# 06_SAMA7G54-PMIC.net
KiCad netlist of a schematic drawn in Altium Designer
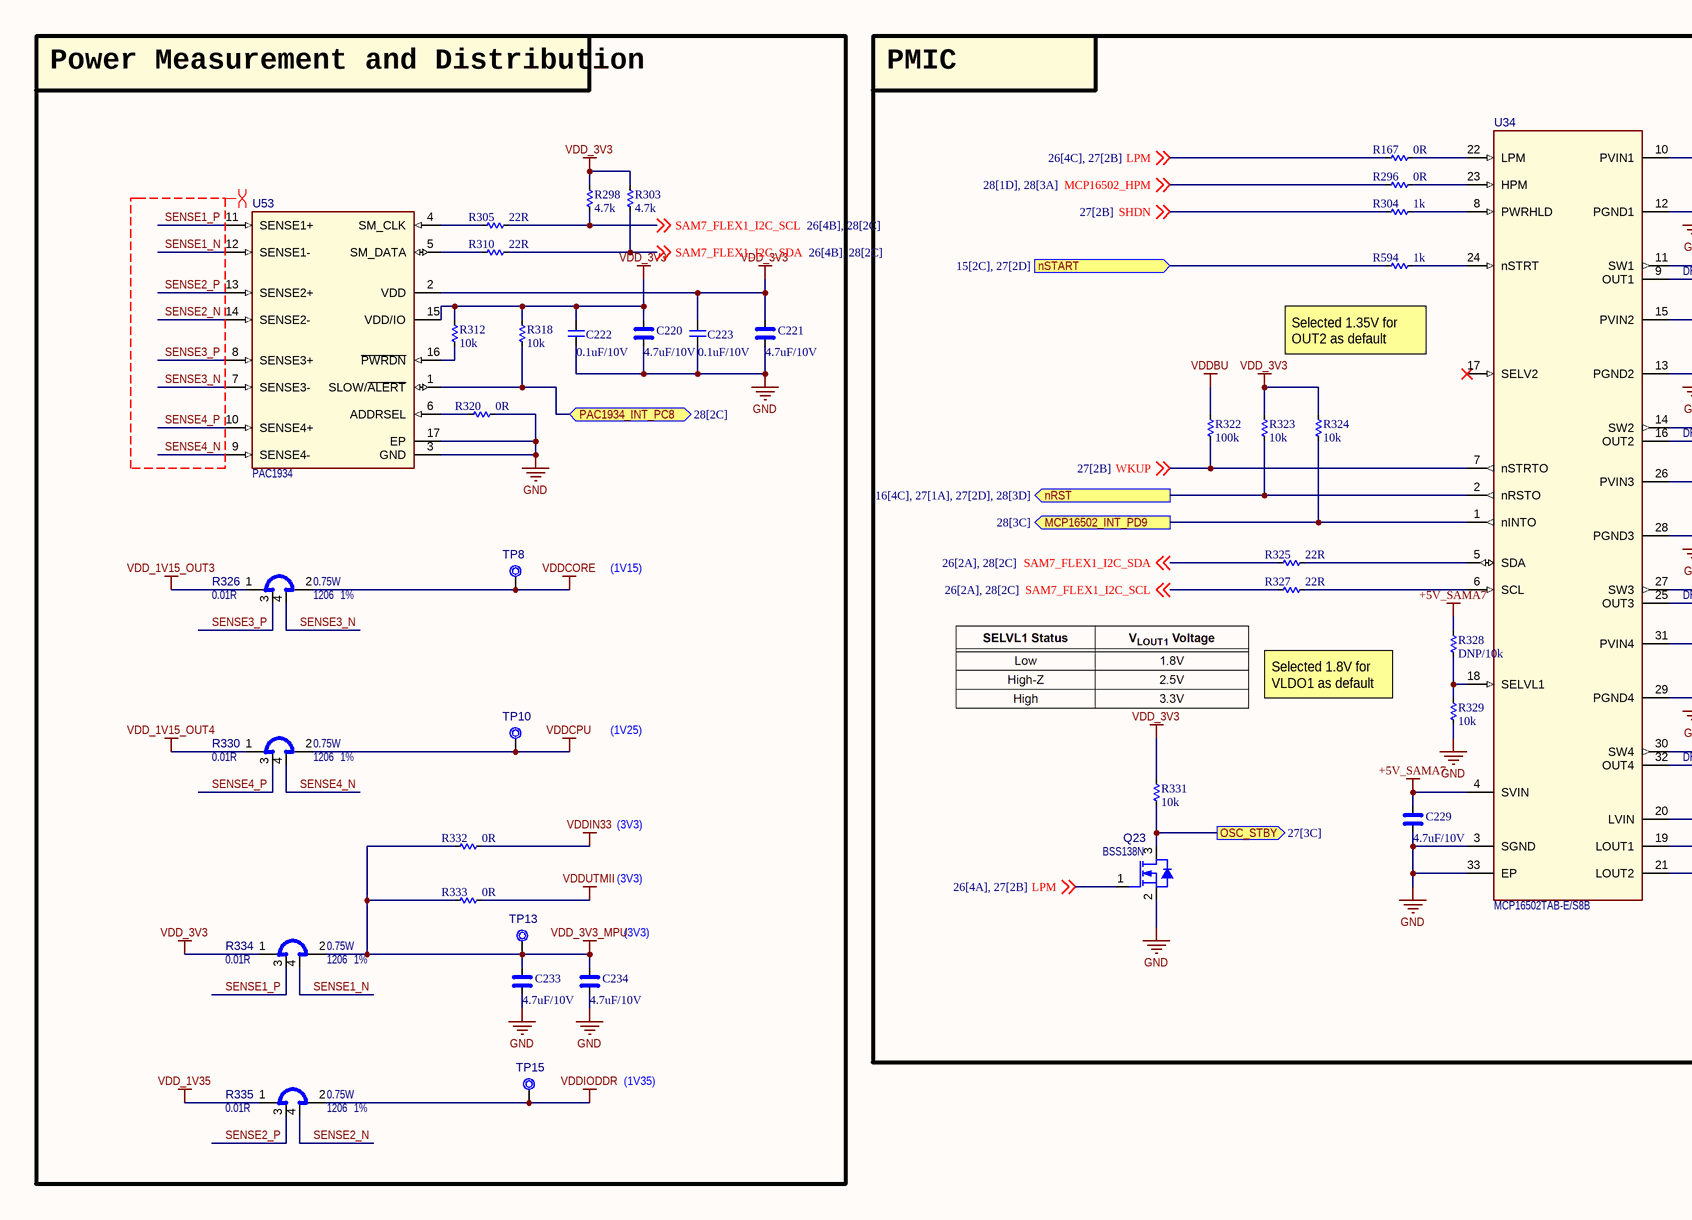
[diagram p0: 06_SAMA7G54-PMIC.SchDoc, left]
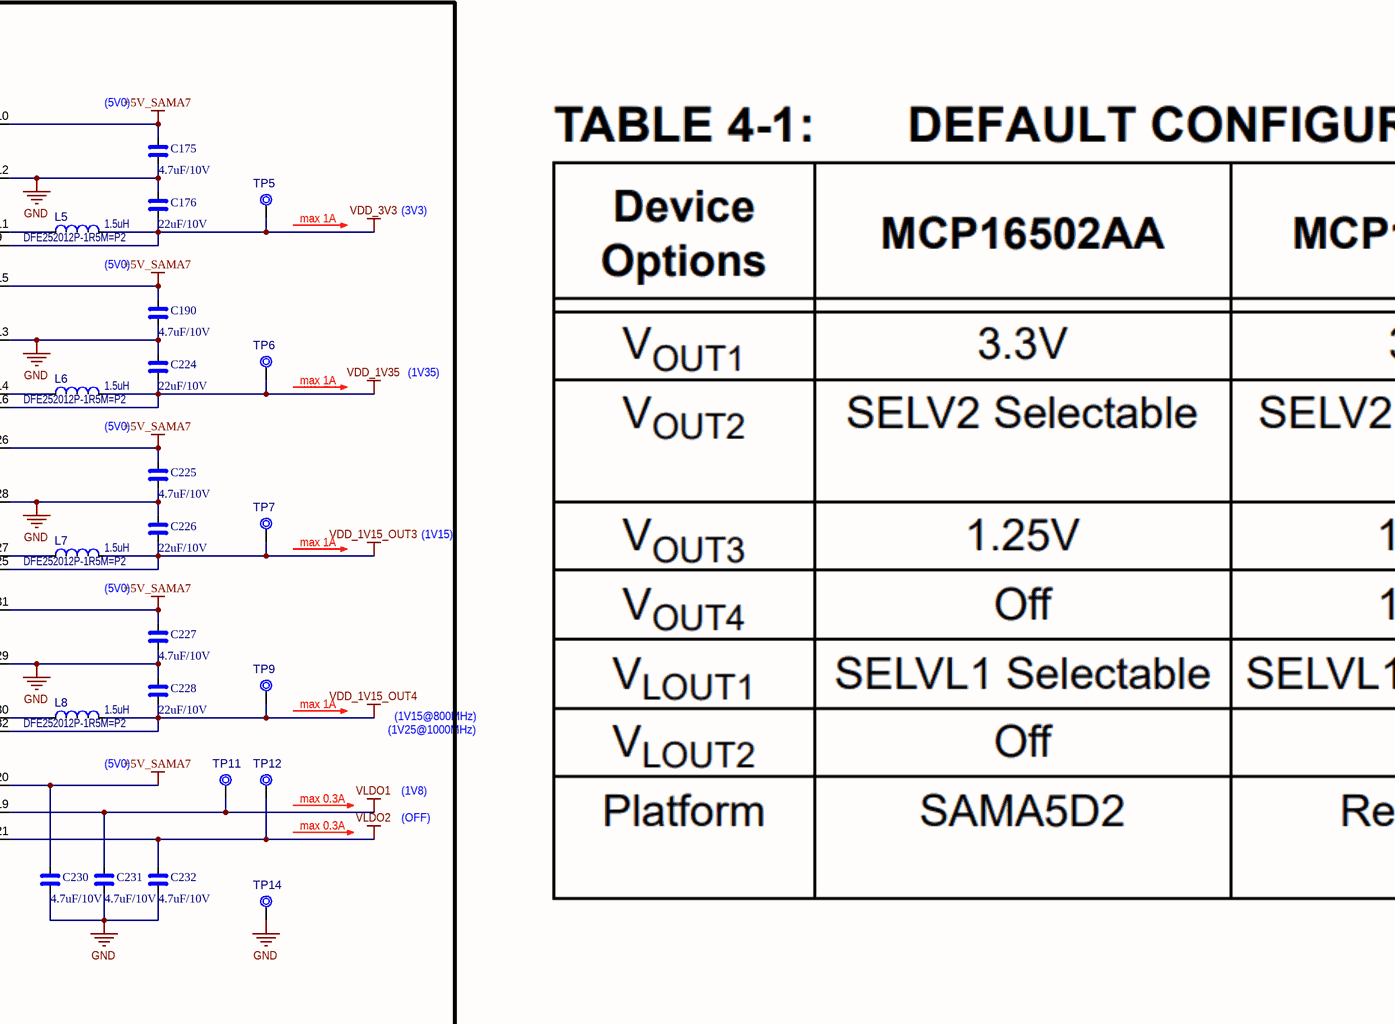
[diagram p1: 06_SAMA7G54-PMIC.SchDoc, middle]
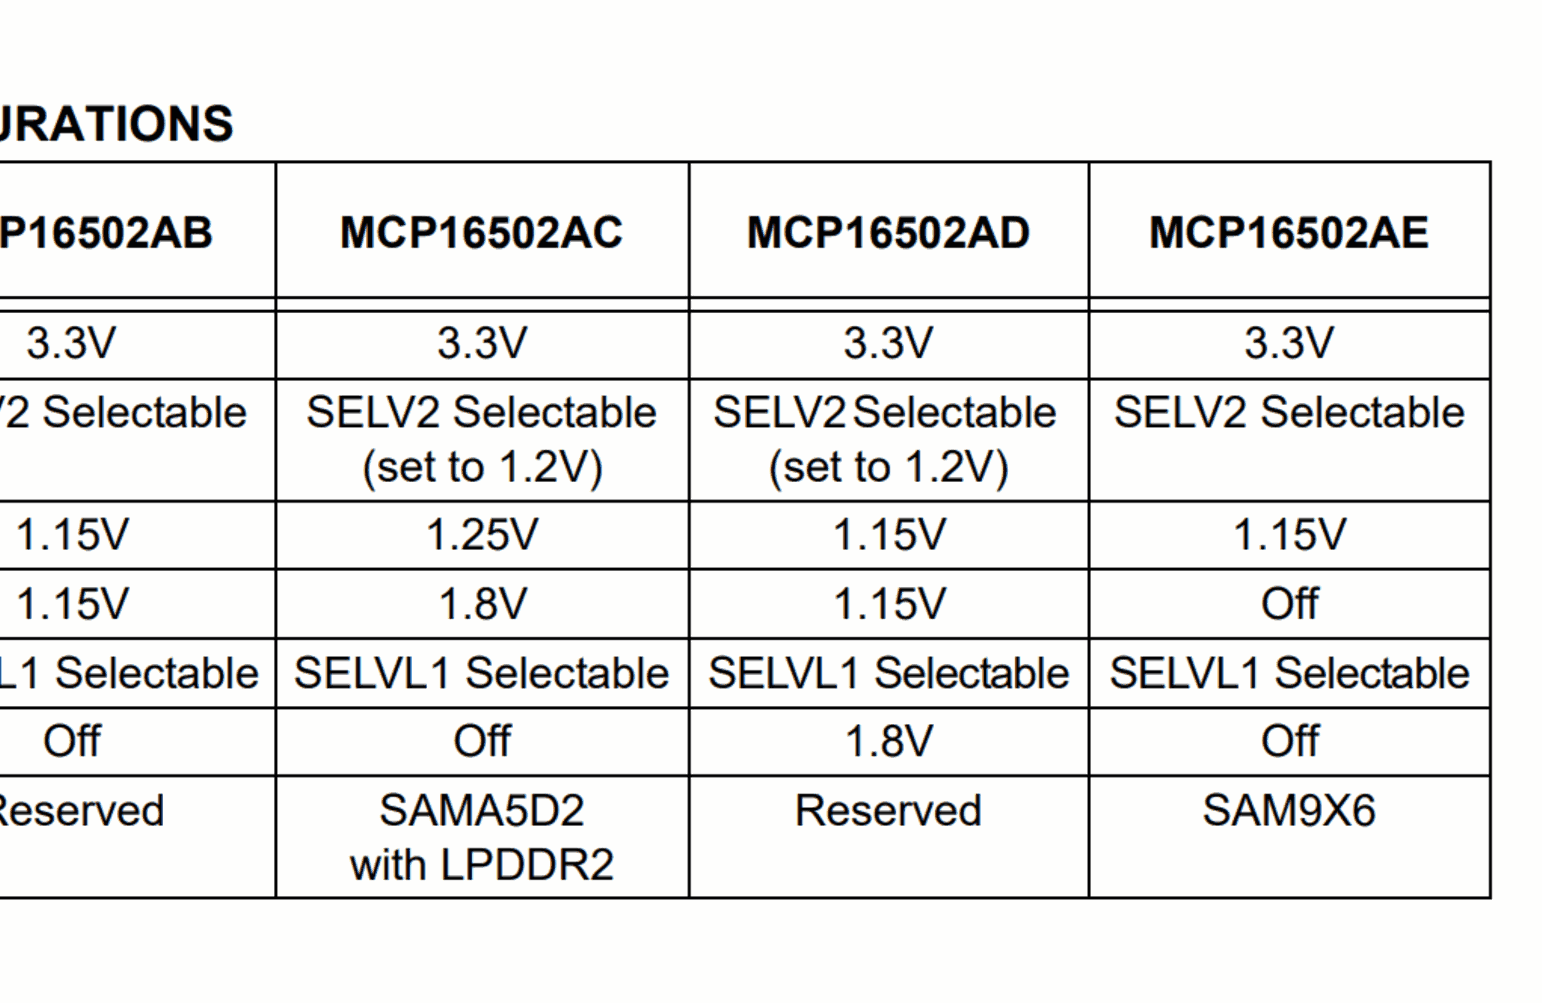
[diagram p2: 06_SAMA7G54-PMIC.SchDoc, right]

(export (version "E")
  (design (tool "Eeschema 10.0.6"))
  (components
    (comp (ref "C175")
      (value "4.7uF/10V")
      (footprint "CAP_C_1005X50_L")
      (description "CAP CHIP High Value")
      (libsource (lib "LABLIB") (part "_CAP_C_High_2"))
    )
    (comp (ref "C176")
      (value "22uF/10V")
      (footprint "CAP_C_1608X80")
      (description "CAP CHIP High Value")
      (libsource (lib "LABLIB") (part "_CAP_C_High_2"))
    )
    (comp (ref "C190")
      (value "4.7uF/10V")
      (footprint "CAP_C_1005X50_L")
      (description "CAP CHIP High Value")
      (libsource (lib "LABLIB") (part "_CAP_C_High_2"))
    )
    (comp (ref "C220")
      (value "4.7uF/10V")
      (footprint "CAP_C_1005X60")
      (description "CAP CHIP High Value")
      (libsource (lib "LABLIB") (part "_CAP_C_High_2"))
    )
    (comp (ref "C221")
      (value "4.7uF/10V")
      (footprint "CAP_C_1005X60")
      (description "CAP CHIP High Value")
      (libsource (lib "LABLIB") (part "_CAP_C_High_2"))
    )
    (comp (ref "C222")
      (value "0.1uF/10V")
      (footprint "CAP_C_1005X60")
      (description "CAP CHIP")
      (libsource (lib "LABLIB") (part "_CAP_C_2"))
    )
    (comp (ref "C223")
      (value "0.1uF/10V")
      (footprint "CAP_C_1005X60")
      (description "CAP CHIP")
      (libsource (lib "LABLIB") (part "_CAP_C_2"))
    )
    (comp (ref "C224")
      (value "22uF/10V")
      (footprint "CAP_C_1608X80")
      (description "CAP CHIP High Value")
      (libsource (lib "LABLIB") (part "_CAP_C_High_2"))
    )
    (comp (ref "C225")
      (value "4.7uF/10V")
      (footprint "CAP_C_1005X50_L")
      (description "CAP CHIP High Value")
      (libsource (lib "LABLIB") (part "_CAP_C_High_2"))
    )
    (comp (ref "C226")
      (value "22uF/10V")
      (footprint "CAP_C_1608X80")
      (description "CAP CHIP High Value")
      (libsource (lib "LABLIB") (part "_CAP_C_High_2"))
    )
    (comp (ref "C227")
      (value "4.7uF/10V")
      (footprint "CAP_C_1005X50_L")
      (description "CAP CHIP High Value")
      (libsource (lib "LABLIB") (part "_CAP_C_High_2"))
    )
    (comp (ref "C228")
      (value "22uF/10V")
      (footprint "CAP_C_1608X80")
      (description "CAP CHIP High Value")
      (libsource (lib "LABLIB") (part "_CAP_C_High_2"))
    )
    (comp (ref "C229")
      (value "4.7uF/10V")
      (footprint "CAP_C_1005X50_L")
      (description "CAP CHIP High Value")
      (libsource (lib "LABLIB") (part "_CAP_C_High_2"))
    )
    (comp (ref "C230")
      (value "4.7uF/10V")
      (footprint "CAP_C_1005X50_L")
      (description "CAP CHIP High Value")
      (libsource (lib "LABLIB") (part "_CAP_C_High_2"))
    )
    (comp (ref "C231")
      (value "4.7uF/10V")
      (footprint "CAP_C_1005X50_L")
      (description "CAP CHIP High Value")
      (libsource (lib "LABLIB") (part "_CAP_C_High_2"))
    )
    (comp (ref "C232")
      (value "4.7uF/10V")
      (footprint "CAP_C_1005X50_L")
      (description "CAP CHIP High Value")
      (libsource (lib "LABLIB") (part "_CAP_C_High_2"))
    )
    (comp (ref "C233")
      (value "4.7uF/10V")
      (footprint "CAP_C_1005X60")
      (description "CAP CHIP High Value")
      (libsource (lib "LABLIB") (part "_CAP_C_High_2"))
    )
    (comp (ref "C234")
      (value "4.7uF/10V")
      (footprint "CAP_C_1005X60")
      (description "CAP CHIP High Value")
      (libsource (lib "LABLIB") (part "_CAP_C_High_2"))
    )
    (comp (ref "L5")
      (value "1.5uH")
      (footprint "IND_C_1008")
      (description "Inductor")
      (fields
        (field (name "MANUFACTURER PART NUMBER 1") "DFE252012P-1R5M=P2")
        (field (name "OWNER") "Razvan Cristescu")
      )
      (libsource (lib "MCHP-CDB") (part "Inductor"))
    )
    (comp (ref "L6")
      (value "1.5uH")
      (footprint "IND_C_1008")
      (description "Inductor")
      (fields
        (field (name "MANUFACTURER PART NUMBER 1") "DFE252012P-1R5M=P2")
        (field (name "OWNER") "Razvan Cristescu")
      )
      (libsource (lib "MCHP-CDB") (part "Inductor"))
    )
    (comp (ref "L7")
      (value "1.5uH")
      (footprint "IND_C_1008")
      (description "Inductor")
      (fields
        (field (name "MANUFACTURER PART NUMBER 1") "DFE252012P-1R5M=P2")
        (field (name "OWNER") "Razvan Cristescu")
      )
      (libsource (lib "MCHP-CDB") (part "Inductor"))
    )
    (comp (ref "L8")
      (value "1.5uH")
      (footprint "IND_C_1008")
      (description "Inductor")
      (fields
        (field (name "MANUFACTURER PART NUMBER 1") "DFE252012P-1R5M=P2")
        (field (name "OWNER") "Razvan Cristescu")
      )
      (libsource (lib "MCHP-CDB") (part "Inductor"))
    )
    (comp (ref "Q23")
      (value "BSS138N")
      (footprint "SOT-23-3")
      (description "Transistor MOS")
      (fields
        (field (name "POWER") "0.36W")
        (field (name "VOLTAGE") "60V")
        (field (name "OWNER") "Dragos Danaila")
      )
      (libsource (lib "MCHP-CDB") (part "Transistor MOS-N GSD"))
    )
    (comp (ref "R167")
      (value "0R")
      (footprint "RES_C_1608X60")
      (description "RES")
      (libsource (lib "LABLIB") (part "_RES_B_2"))
    )
    (comp (ref "R296")
      (value "0R")
      (footprint "RES_C_1608X60")
      (description "RES")
      (libsource (lib "LABLIB") (part "_RES_B_2"))
    )
    (comp (ref "R298")
      (value "4.7k")
      (footprint "RES_C_1005X40")
      (description "RES")
      (libsource (lib "LABLIB") (part "_RES_B_2"))
    )
    (comp (ref "R303")
      (value "4.7k")
      (footprint "RES_C_1005X40")
      (description "RES")
      (libsource (lib "LABLIB") (part "_RES_B_2"))
    )
    (comp (ref "R304")
      (value "1k")
      (footprint "RES_C_1005X40")
      (description "RES")
      (libsource (lib "LABLIB") (part "_RES_B_2"))
    )
    (comp (ref "R305")
      (value "22R")
      (footprint "RES_C_1005X40")
      (description "RES")
      (libsource (lib "LABLIB") (part "_RES_B_2"))
    )
    (comp (ref "R310")
      (value "22R")
      (footprint "RES_C_1005X40")
      (description "RES")
      (libsource (lib "LABLIB") (part "_RES_B_2"))
    )
    (comp (ref "R312")
      (value "10k")
      (footprint "RES_C_1005X40")
      (description "RES")
      (libsource (lib "LABLIB") (part "_RES_B_2"))
    )
    (comp (ref "R318")
      (value "10k")
      (footprint "RES_C_1005X40")
      (description "RES")
      (libsource (lib "LABLIB") (part "_RES_B_2"))
    )
    (comp (ref "R320")
      (value "0R")
      (footprint "RES_C_1005X40")
      (description "RES")
      (libsource (lib "LABLIB") (part "_RES_B_2"))
    )
    (comp (ref "R322")
      (value "100k")
      (footprint "RES_C_1005X40")
      (description "RES")
      (libsource (lib "LABLIB") (part "_RES_B_2"))
    )
    (comp (ref "R323")
      (value "10k")
      (footprint "RES_C_1005X40")
      (description "RES")
      (libsource (lib "LABLIB") (part "_RES_B_2"))
    )
    (comp (ref "R324")
      (value "10k")
      (footprint "RES_C_1005X40")
      (description "RES")
      (libsource (lib "LABLIB") (part "_RES_B_2"))
    )
    (comp (ref "R325")
      (value "22R")
      (footprint "RES_C_0603X30")
      (description "RES")
      (libsource (lib "LABLIB") (part "_RES_B_2"))
    )
    (comp (ref "R326")
      (value "0.01R")
      (footprint "RES_C_1206_SHUNT")
      (description "Shunt")
      (fields
        (field (name "PACKAGE") "1206")
        (field (name "TOLERANCE") "1%")
        (field (name "POWER") "0.75W")
        (field (name "Comment") "Shunt 4 Pin")
        (field (name "OWNER") "Ciprian Abramov")
      )
      (libsource (lib "MCHP-CDB") (part "Shunt 4 Pin"))
    )
    (comp (ref "R327")
      (value "22R")
      (footprint "RES_C_0603X30")
      (description "RES")
      (libsource (lib "LABLIB") (part "_RES_B_2"))
    )
    (comp (ref "R328")
      (value "DNP/10k")
      (footprint "RES_C_1005X40")
      (description "RES")
      (libsource (lib "LABLIB") (part "_RES_B_2"))
    )
    (comp (ref "R329")
      (value "10k")
      (footprint "RES_C_1005X40")
      (description "RES")
      (libsource (lib "LABLIB") (part "_RES_B_2"))
    )
    (comp (ref "R330")
      (value "0.01R")
      (footprint "RES_C_1206_SHUNT")
      (description "Shunt")
      (fields
        (field (name "PACKAGE") "1206")
        (field (name "TOLERANCE") "1%")
        (field (name "POWER") "0.75W")
        (field (name "Comment") "Shunt 4 Pin")
        (field (name "OWNER") "Ciprian Abramov")
      )
      (libsource (lib "MCHP-CDB") (part "Shunt 4 Pin"))
    )
    (comp (ref "R331")
      (value "10k")
      (footprint "RES_C_1005X40")
      (description "RES")
      (libsource (lib "LABLIB") (part "_RES_B_2"))
    )
    (comp (ref "R332")
      (value "0R")
      (footprint "RES_C_1608X60")
      (description "RES")
      (libsource (lib "LABLIB") (part "_RES_B_2"))
    )
    (comp (ref "R333")
      (value "0R")
      (footprint "RES_C_1608X60")
      (description "RES")
      (libsource (lib "LABLIB") (part "_RES_B_2"))
    )
    (comp (ref "R334")
      (value "0.01R")
      (footprint "RES_C_1206_SHUNT")
      (description "Shunt")
      (fields
        (field (name "PACKAGE") "1206")
        (field (name "TOLERANCE") "1%")
        (field (name "POWER") "0.75W")
        (field (name "Comment") "Shunt 4 Pin")
        (field (name "OWNER") "Ciprian Abramov")
      )
      (libsource (lib "MCHP-CDB") (part "Shunt 4 Pin"))
    )
    (comp (ref "R335")
      (value "0.01R")
      (footprint "RES_C_1206_SHUNT")
      (description "Shunt")
      (fields
        (field (name "PACKAGE") "1206")
        (field (name "TOLERANCE") "1%")
        (field (name "POWER") "0.75W")
        (field (name "Comment") "Shunt 4 Pin")
        (field (name "OWNER") "Ciprian Abramov")
      )
      (libsource (lib "MCHP-CDB") (part "Shunt 4 Pin"))
    )
    (comp (ref "R594")
      (value "1k")
      (footprint "RES_C_1005X40")
      (description "RES")
      (libsource (lib "LABLIB") (part "_RES_B_2"))
    )
    (comp (ref "TP5")
      (value "Test Point No BOM")
      (footprint "Testpoint_80")
      (description "Test Point")
      (fields (field (name "OWNER") "Cristian Papuc"))
      (libsource (lib "MCHP-CDB") (part "Test Point No BOM"))
    )
    (comp (ref "TP6")
      (value "Test Point No BOM")
      (footprint "Testpoint_80")
      (description "Test Point")
      (fields (field (name "OWNER") "Cristian Papuc"))
      (libsource (lib "MCHP-CDB") (part "Test Point No BOM"))
    )
    (comp (ref "TP7")
      (value "Test Point No BOM")
      (footprint "Testpoint_80")
      (description "Test Point")
      (fields (field (name "OWNER") "Cristian Papuc"))
      (libsource (lib "MCHP-CDB") (part "Test Point No BOM"))
    )
    (comp (ref "TP8")
      (value "Test Point No BOM")
      (footprint "Testpoint_80")
      (description "Test Point")
      (fields (field (name "OWNER") "Cristian Papuc"))
      (libsource (lib "MCHP-CDB") (part "Test Point No BOM"))
    )
    (comp (ref "TP9")
      (value "Test Point No BOM")
      (footprint "Testpoint_80")
      (description "Test Point")
      (fields (field (name "OWNER") "Cristian Papuc"))
      (libsource (lib "MCHP-CDB") (part "Test Point No BOM"))
    )
    (comp (ref "TP10")
      (value "Test Point No BOM")
      (footprint "Testpoint_80")
      (description "Test Point")
      (fields (field (name "OWNER") "Cristian Papuc"))
      (libsource (lib "MCHP-CDB") (part "Test Point No BOM"))
    )
    (comp (ref "TP11")
      (value "Test Point No BOM")
      (footprint "Testpoint_80")
      (description "Test Point")
      (fields (field (name "OWNER") "Cristian Papuc"))
      (libsource (lib "MCHP-CDB") (part "Test Point No BOM"))
    )
    (comp (ref "TP12")
      (value "Test Point No BOM")
      (footprint "Testpoint_80")
      (description "Test Point")
      (fields (field (name "OWNER") "Cristian Papuc"))
      (libsource (lib "MCHP-CDB") (part "Test Point No BOM"))
    )
    (comp (ref "TP13")
      (value "Test Point No BOM")
      (footprint "Testpoint_80")
      (description "Test Point")
      (fields (field (name "OWNER") "Cristian Papuc"))
      (libsource (lib "MCHP-CDB") (part "Test Point No BOM"))
    )
    (comp (ref "TP14")
      (value "Test Point No BOM")
      (footprint "Testpoint_80")
      (description "Test Point")
      (fields (field (name "OWNER") "Cristian Papuc"))
      (libsource (lib "MCHP-CDB") (part "Test Point No BOM"))
    )
    (comp (ref "TP15")
      (value "Test Point No BOM")
      (footprint "Testpoint_80")
      (description "Test Point")
      (fields (field (name "OWNER") "Cristian Papuc"))
      (libsource (lib "MCHP-CDB") (part "Test Point No BOM"))
    )
    (comp (ref "U34")
      (value "MCP16502TAB-E/S8B")
      (footprint "QFN-32_5X5_EP3.7X3.7")
      (fields (field (name "OWNER") "Dragos Danaila"))
      (libsource (lib "MCHP-CDB") (part "MCP16502 QFN-32"))
    )
    (comp (ref "U53")
      (value "PAC1934")
      (footprint "UQFN-16_4X4_EP2.6X2.6")
      (fields (field (name "Comment") "PAC1934 UQFN-16") (field (name "OWNER") "Ciprian Abramov"))
      (libsource (lib "MCHP-CDB") (part "PAC1934 UQFN-16"))
    )
  )
  (nets
    (net (code "1") (name "+5V_SAMA7") (class "Default")
      (node (ref "C175") (pin "1") (pinfunction "1_1") (pintype "passive"))
      (node (ref "C190") (pin "1") (pinfunction "1_1") (pintype "passive"))
      (node (ref "C225") (pin "1") (pinfunction "1_1") (pintype "passive"))
      (node (ref "C227") (pin "1") (pinfunction "1_1") (pintype "passive"))
      (node (ref "C229") (pin "1") (pinfunction "1_1") (pintype "passive"))
      (node (ref "C230") (pin "1") (pinfunction "1_1") (pintype "passive"))
      (node (ref "R328") (pin "2") (pinfunction "2_2") (pintype "passive"))
      (node (ref "U34") (pin "10") (pinfunction "PVIN1_10") (pintype "power_in"))
      (node (ref "U34") (pin "15") (pinfunction "PVIN2_15") (pintype "power_in"))
      (node (ref "U34") (pin "20") (pinfunction "LVIN_20") (pintype "power_in"))
      (node (ref "U34") (pin "26") (pinfunction "PVIN3_26") (pintype "power_in"))
      (node (ref "U34") (pin "31") (pinfunction "PVIN4_31") (pintype "power_in"))
      (node (ref "U34") (pin "4") (pinfunction "SVIN_4") (pintype "power_in"))
    )
    (net (code "2") (name "/MCP16502_INT_PD9") (class "Default")
      (node (ref "R324") (pin "1") (pinfunction "1_1") (pintype "passive"))
      (node (ref "U34") (pin "1") (pinfunction "nINTO_1") (pintype "output"))
    )
    (net (code "3") (name "/OSC_STBY") (class "Default")
      (node (ref "Q23") (pin "3") (pinfunction "D_3") (pintype "passive"))
      (node (ref "R331") (pin "1") (pinfunction "1_1") (pintype "passive"))
    )
    (net (code "4") (name "/PAC1934_INT_PC8") (class "Default")
      (node (ref "R318") (pin "2") (pinfunction "2_2") (pintype "passive"))
      (node (ref "U53") (pin "1") (pinfunction "SLOW/~{ALERT}_1") (pintype "bidirectional"))
    )
    (net (code "5") (name "/SENSE1_N") (class "Default")
      (node (ref "R334") (pin "4") (pinfunction "4_4") (pintype "passive"))
      (node (ref "U53") (pin "12") (pinfunction "SENSE1-_12") (pintype "input"))
    )
    (net (code "6") (name "/SENSE1_P") (class "Default")
      (node (ref "R334") (pin "3") (pinfunction "3_3") (pintype "passive"))
      (node (ref "U53") (pin "11") (pinfunction "SENSE1+_11") (pintype "input"))
    )
    (net (code "7") (name "/SENSE2_N") (class "Default")
      (node (ref "R335") (pin "4") (pinfunction "4_4") (pintype "passive"))
      (node (ref "U53") (pin "14") (pinfunction "SENSE2-_14") (pintype "input"))
    )
    (net (code "8") (name "/SENSE2_P") (class "Default")
      (node (ref "R335") (pin "3") (pinfunction "3_3") (pintype "passive"))
      (node (ref "U53") (pin "13") (pinfunction "SENSE2+_13") (pintype "input"))
    )
    (net (code "9") (name "/SENSE3_N") (class "Default")
      (node (ref "R326") (pin "4") (pinfunction "4_4") (pintype "passive"))
      (node (ref "U53") (pin "7") (pinfunction "SENSE3-_7") (pintype "input"))
    )
    (net (code "10") (name "/SENSE3_P") (class "Default")
      (node (ref "R326") (pin "3") (pinfunction "3_3") (pintype "passive"))
      (node (ref "U53") (pin "8") (pinfunction "SENSE3+_8") (pintype "input"))
    )
    (net (code "11") (name "/SENSE4_N") (class "Default")
      (node (ref "R330") (pin "4") (pinfunction "4_4") (pintype "passive"))
      (node (ref "U53") (pin "9") (pinfunction "SENSE4-_9") (pintype "input"))
    )
    (net (code "12") (name "/SENSE4_P") (class "Default")
      (node (ref "R330") (pin "3") (pinfunction "3_3") (pintype "passive"))
      (node (ref "U53") (pin "10") (pinfunction "SENSE4+_10") (pintype "input"))
    )
    (net (code "13") (name "/nRST") (class "Default")
      (node (ref "R323") (pin "1") (pinfunction "1_1") (pintype "passive"))
      (node (ref "U34") (pin "2") (pinfunction "nRSTO_2") (pintype "output"))
    )
    (net (code "14") (name "/nSTART") (class "Default")
      (node (ref "R594") (pin "1") (pinfunction "1_1") (pintype "passive"))
    )
    (net (code "15") (name "GND") (class "Default")
      (node (ref "C175") (pin "2") (pinfunction "2_2") (pintype "passive"))
      (node (ref "C176") (pin "1") (pinfunction "1_1") (pintype "passive"))
      (node (ref "C190") (pin "2") (pinfunction "2_2") (pintype "passive"))
      (node (ref "C220") (pin "2") (pinfunction "2_2") (pintype "passive"))
      (node (ref "C221") (pin "2") (pinfunction "2_2") (pintype "passive"))
      (node (ref "C222") (pin "2") (pinfunction "2_2") (pintype "passive"))
      (node (ref "C223") (pin "2") (pinfunction "2_2") (pintype "passive"))
      (node (ref "C224") (pin "1") (pinfunction "1_1") (pintype "passive"))
      (node (ref "C225") (pin "2") (pinfunction "2_2") (pintype "passive"))
      (node (ref "C226") (pin "1") (pinfunction "1_1") (pintype "passive"))
      (node (ref "C227") (pin "2") (pinfunction "2_2") (pintype "passive"))
      (node (ref "C228") (pin "1") (pinfunction "1_1") (pintype "passive"))
      (node (ref "C229") (pin "2") (pinfunction "2_2") (pintype "passive"))
      (node (ref "C230") (pin "2") (pinfunction "2_2") (pintype "passive"))
      (node (ref "C231") (pin "2") (pinfunction "2_2") (pintype "passive"))
      (node (ref "C232") (pin "2") (pinfunction "2_2") (pintype "passive"))
      (node (ref "C233") (pin "2") (pinfunction "2_2") (pintype "passive"))
      (node (ref "C234") (pin "2") (pinfunction "2_2") (pintype "passive"))
      (node (ref "Q23") (pin "2") (pinfunction "S_2") (pintype "passive"))
      (node (ref "R320") (pin "2") (pinfunction "2_2") (pintype "passive"))
      (node (ref "R329") (pin "1") (pinfunction "1_1") (pintype "passive"))
      (node (ref "TP14") (pin "1") (pinfunction "1_1") (pintype "passive"))
      (node (ref "U34") (pin "12") (pinfunction "PGND1_12") (pintype "power_in"))
      (node (ref "U34") (pin "13") (pinfunction "PGND2_13") (pintype "power_in"))
      (node (ref "U34") (pin "28") (pinfunction "PGND3_28") (pintype "power_in"))
      (node (ref "U34") (pin "29") (pinfunction "PGND4_29") (pintype "power_in"))
      (node (ref "U34") (pin "3") (pinfunction "SGND_3") (pintype "power_in"))
      (node (ref "U34") (pin "33") (pinfunction "EP_33") (pintype "power_in"))
      (node (ref "U53") (pin "17") (pinfunction "EP_17") (pintype "passive"))
      (node (ref "U53") (pin "3") (pinfunction "GND_3") (pintype "power_in"))
    )
    (net (code "16") (name "LPM") (class "Default")
      (node (ref "Q23") (pin "1") (pinfunction "G_1") (pintype "passive"))
      (node (ref "R167") (pin "2") (pinfunction "2_2") (pintype "passive"))
    )
    (net (code "17") (name "MCP16502_HPM") (class "Default")
      (node (ref "R296") (pin "2") (pinfunction "2_2") (pintype "passive"))
    )
    (net (code "18") (name "Net-(L5-S)") (class "Default")
      (node (ref "L5") (pin "1") (pinfunction "S_1") (pintype "passive"))
      (node (ref "U34") (pin "11") (pinfunction "SW1_11") (pintype "output"))
    )
    (net (code "19") (name "Net-(L6-S)") (class "Default")
      (node (ref "L6") (pin "1") (pinfunction "S_1") (pintype "passive"))
      (node (ref "U34") (pin "14") (pinfunction "SW2_14") (pintype "output"))
    )
    (net (code "20") (name "Net-(L7-S)") (class "Default")
      (node (ref "L7") (pin "1") (pinfunction "S_1") (pintype "passive"))
      (node (ref "U34") (pin "27") (pinfunction "SW3_27") (pintype "output"))
    )
    (net (code "21") (name "Net-(L8-S)") (class "Default")
      (node (ref "L8") (pin "1") (pinfunction "S_1") (pintype "passive"))
      (node (ref "U34") (pin "30") (pinfunction "SW4_30") (pintype "output"))
    )
    (net (code "22") (name "Net-(U34-HPM)") (class "Default")
      (node (ref "R296") (pin "1") (pinfunction "1_1") (pintype "passive"))
      (node (ref "U34") (pin "23") (pinfunction "HPM_23") (pintype "input"))
    )
    (net (code "23") (name "Net-(U34-LPM)") (class "Default")
      (node (ref "R167") (pin "1") (pinfunction "1_1") (pintype "passive"))
      (node (ref "U34") (pin "22") (pinfunction "LPM_22") (pintype "input"))
    )
    (net (code "24") (name "Net-(U34-PWRHLD)") (class "Default")
      (node (ref "R304") (pin "2") (pinfunction "2_2") (pintype "passive"))
      (node (ref "U34") (pin "8") (pinfunction "PWRHLD_8") (pintype "input"))
    )
    (net (code "25") (name "Net-(U34-SCL)") (class "Default")
      (node (ref "R327") (pin "1") (pinfunction "1_1") (pintype "passive"))
      (node (ref "U34") (pin "6") (pinfunction "SCL_6") (pintype "input"))
    )
    (net (code "26") (name "Net-(U34-SDA)") (class "Default")
      (node (ref "R325") (pin "1") (pinfunction "1_1") (pintype "passive"))
      (node (ref "U34") (pin "5") (pinfunction "SDA_5") (pintype "bidirectional"))
    )
    (net (code "27") (name "Net-(U34-SELVL1)") (class "Default")
      (node (ref "R328") (pin "1") (pinfunction "1_1") (pintype "passive"))
      (node (ref "R329") (pin "2") (pinfunction "2_2") (pintype "passive"))
      (node (ref "U34") (pin "18") (pinfunction "SELVL1_18") (pintype "input"))
    )
    (net (code "28") (name "Net-(U34-nSTRT)") (class "Default")
      (node (ref "R594") (pin "2") (pinfunction "2_2") (pintype "passive"))
      (node (ref "U34") (pin "24") (pinfunction "nSTRT_24") (pintype "input"))
    )
    (net (code "29") (name "Net-(U53-ADDRSEL)") (class "Default")
      (node (ref "R320") (pin "1") (pinfunction "1_1") (pintype "passive"))
      (node (ref "U53") (pin "6") (pinfunction "ADDRSEL_6") (pintype "input"))
    )
    (net (code "30") (name "Net-(U53-SM_CLK)") (class "Default")
      (node (ref "R305") (pin "2") (pinfunction "2_2") (pintype "passive"))
      (node (ref "U53") (pin "4") (pinfunction "SM_CLK_4") (pintype "input"))
    )
    (net (code "31") (name "Net-(U53-SM_DATA)") (class "Default")
      (node (ref "R310") (pin "2") (pinfunction "2_2") (pintype "passive"))
      (node (ref "U53") (pin "5") (pinfunction "SM_DATA_5") (pintype "bidirectional"))
    )
    (net (code "32") (name "Net-(U53-~{PWRDN})") (class "Default")
      (node (ref "R312") (pin "2") (pinfunction "2_2") (pintype "passive"))
      (node (ref "U53") (pin "16") (pinfunction "~{PWRDN}_16") (pintype "input"))
    )
    (net (code "33") (name "SAM7_FLEX1_I2C_SCL") (class "Default")
      (node (ref "R298") (pin "2") (pinfunction "2_2") (pintype "passive"))
      (node (ref "R305") (pin "1") (pinfunction "1_1") (pintype "passive"))
      (node (ref "R327") (pin "2") (pinfunction "2_2") (pintype "passive"))
    )
    (net (code "34") (name "SAM7_FLEX1_I2C_SDA") (class "Default")
      (node (ref "R303") (pin "2") (pinfunction "2_2") (pintype "passive"))
      (node (ref "R310") (pin "1") (pinfunction "1_1") (pintype "passive"))
      (node (ref "R325") (pin "2") (pinfunction "2_2") (pintype "passive"))
    )
    (net (code "35") (name "SHDN") (class "Default")
      (node (ref "R304") (pin "1") (pinfunction "1_1") (pintype "passive"))
    )
    (net (code "36") (name "VDDBU") (class "Default")
      (node (ref "R322") (pin "2") (pinfunction "2_2") (pintype "passive"))
    )
    (net (code "37") (name "VDDCORE") (class "Default")
      (node (ref "R326") (pin "2") (pinfunction "2_2") (pintype "passive"))
      (node (ref "TP8") (pin "1") (pinfunction "1_1") (pintype "passive"))
    )
    (net (code "38") (name "VDDCPU") (class "Default")
      (node (ref "R330") (pin "2") (pinfunction "2_2") (pintype "passive"))
      (node (ref "TP10") (pin "1") (pinfunction "1_1") (pintype "passive"))
    )
    (net (code "39") (name "VDDIN33") (class "Default")
      (node (ref "R332") (pin "1") (pinfunction "1_1") (pintype "passive"))
    )
    (net (code "40") (name "VDDIODDR") (class "Default")
      (node (ref "R335") (pin "2") (pinfunction "2_2") (pintype "passive"))
      (node (ref "TP15") (pin "1") (pinfunction "1_1") (pintype "passive"))
    )
    (net (code "41") (name "VDDUTMII") (class "Default")
      (node (ref "R333") (pin "1") (pinfunction "1_1") (pintype "passive"))
    )
    (net (code "42") (name "VDD_1V15_OUT3") (class "Default")
      (node (ref "C226") (pin "2") (pinfunction "2_2") (pintype "passive"))
      (node (ref "L7") (pin "2") (pinfunction "F_2") (pintype "passive"))
      (node (ref "R326") (pin "1") (pinfunction "1_1") (pintype "passive"))
      (node (ref "TP7") (pin "1") (pinfunction "1_1") (pintype "passive"))
      (node (ref "U34") (pin "25") (pinfunction "OUT3_25") (pintype "power_in"))
    )
    (net (code "43") (name "VDD_1V15_OUT4") (class "Default")
      (node (ref "C228") (pin "2") (pinfunction "2_2") (pintype "passive"))
      (node (ref "L8") (pin "2") (pinfunction "F_2") (pintype "passive"))
      (node (ref "R330") (pin "1") (pinfunction "1_1") (pintype "passive"))
      (node (ref "TP9") (pin "1") (pinfunction "1_1") (pintype "passive"))
      (node (ref "U34") (pin "32") (pinfunction "OUT4_32") (pintype "power_in"))
    )
    (net (code "44") (name "VDD_1V35") (class "Default")
      (node (ref "C224") (pin "2") (pinfunction "2_2") (pintype "passive"))
      (node (ref "L6") (pin "2") (pinfunction "F_2") (pintype "passive"))
      (node (ref "R335") (pin "1") (pinfunction "1_1") (pintype "passive"))
      (node (ref "TP6") (pin "1") (pinfunction "1_1") (pintype "passive"))
      (node (ref "U34") (pin "16") (pinfunction "OUT2_16") (pintype "power_in"))
    )
    (net (code "45") (name "VDD_3V3") (class "Default")
      (node (ref "C176") (pin "2") (pinfunction "2_2") (pintype "passive"))
      (node (ref "C220") (pin "1") (pinfunction "1_1") (pintype "passive"))
      (node (ref "C221") (pin "1") (pinfunction "1_1") (pintype "passive"))
      (node (ref "C222") (pin "1") (pinfunction "1_1") (pintype "passive"))
      (node (ref "C223") (pin "1") (pinfunction "1_1") (pintype "passive"))
      (node (ref "L5") (pin "2") (pinfunction "F_2") (pintype "passive"))
      (node (ref "R298") (pin "1") (pinfunction "1_1") (pintype "passive"))
      (node (ref "R303") (pin "1") (pinfunction "1_1") (pintype "passive"))
      (node (ref "R312") (pin "1") (pinfunction "1_1") (pintype "passive"))
      (node (ref "R318") (pin "1") (pinfunction "1_1") (pintype "passive"))
      (node (ref "R323") (pin "2") (pinfunction "2_2") (pintype "passive"))
      (node (ref "R324") (pin "2") (pinfunction "2_2") (pintype "passive"))
      (node (ref "R331") (pin "2") (pinfunction "2_2") (pintype "passive"))
      (node (ref "R334") (pin "1") (pinfunction "1_1") (pintype "passive"))
      (node (ref "TP5") (pin "1") (pinfunction "1_1") (pintype "passive"))
      (node (ref "U34") (pin "9") (pinfunction "OUT1_9") (pintype "power_in"))
      (node (ref "U53") (pin "15") (pinfunction "VDD/IO_15") (pintype "power_in"))
      (node (ref "U53") (pin "2") (pinfunction "VDD_2") (pintype "power_in"))
    )
    (net (code "46") (name "VDD_3V3_MPU") (class "Default")
      (node (ref "C233") (pin "1") (pinfunction "1_1") (pintype "passive"))
      (node (ref "C234") (pin "1") (pinfunction "1_1") (pintype "passive"))
      (node (ref "R332") (pin "2") (pinfunction "2_2") (pintype "passive"))
      (node (ref "R333") (pin "2") (pinfunction "2_2") (pintype "passive"))
      (node (ref "R334") (pin "2") (pinfunction "2_2") (pintype "passive"))
      (node (ref "TP13") (pin "1") (pinfunction "1_1") (pintype "passive"))
    )
    (net (code "47") (name "VLDO1") (class "Default")
      (node (ref "C231") (pin "1") (pinfunction "1_1") (pintype "passive"))
      (node (ref "TP11") (pin "1") (pinfunction "1_1") (pintype "passive"))
      (node (ref "U34") (pin "19") (pinfunction "LOUT1_19") (pintype "power_in"))
    )
    (net (code "48") (name "VLDO2") (class "Default")
      (node (ref "C232") (pin "1") (pinfunction "1_1") (pintype "passive"))
      (node (ref "TP12") (pin "1") (pinfunction "1_1") (pintype "passive"))
      (node (ref "U34") (pin "21") (pinfunction "LOUT2_21") (pintype "power_in"))
    )
    (net (code "49") (name "WKUP") (class "Default")
      (node (ref "R322") (pin "1") (pinfunction "1_1") (pintype "passive"))
      (node (ref "U34") (pin "7") (pinfunction "nSTRTO_7") (pintype "output"))
    )
    (net (code "50") (name "unconnected-(U34-SELV2-Pad17)") (class "Default")
      (node (ref "U34") (pin "17") (pinfunction "SELV2_17") (pintype "input+no_connect"))
    )
  )
)
